# TOF_Module_v02.net
KiCad netlist of a schematic drawn in EasyEDA Pro
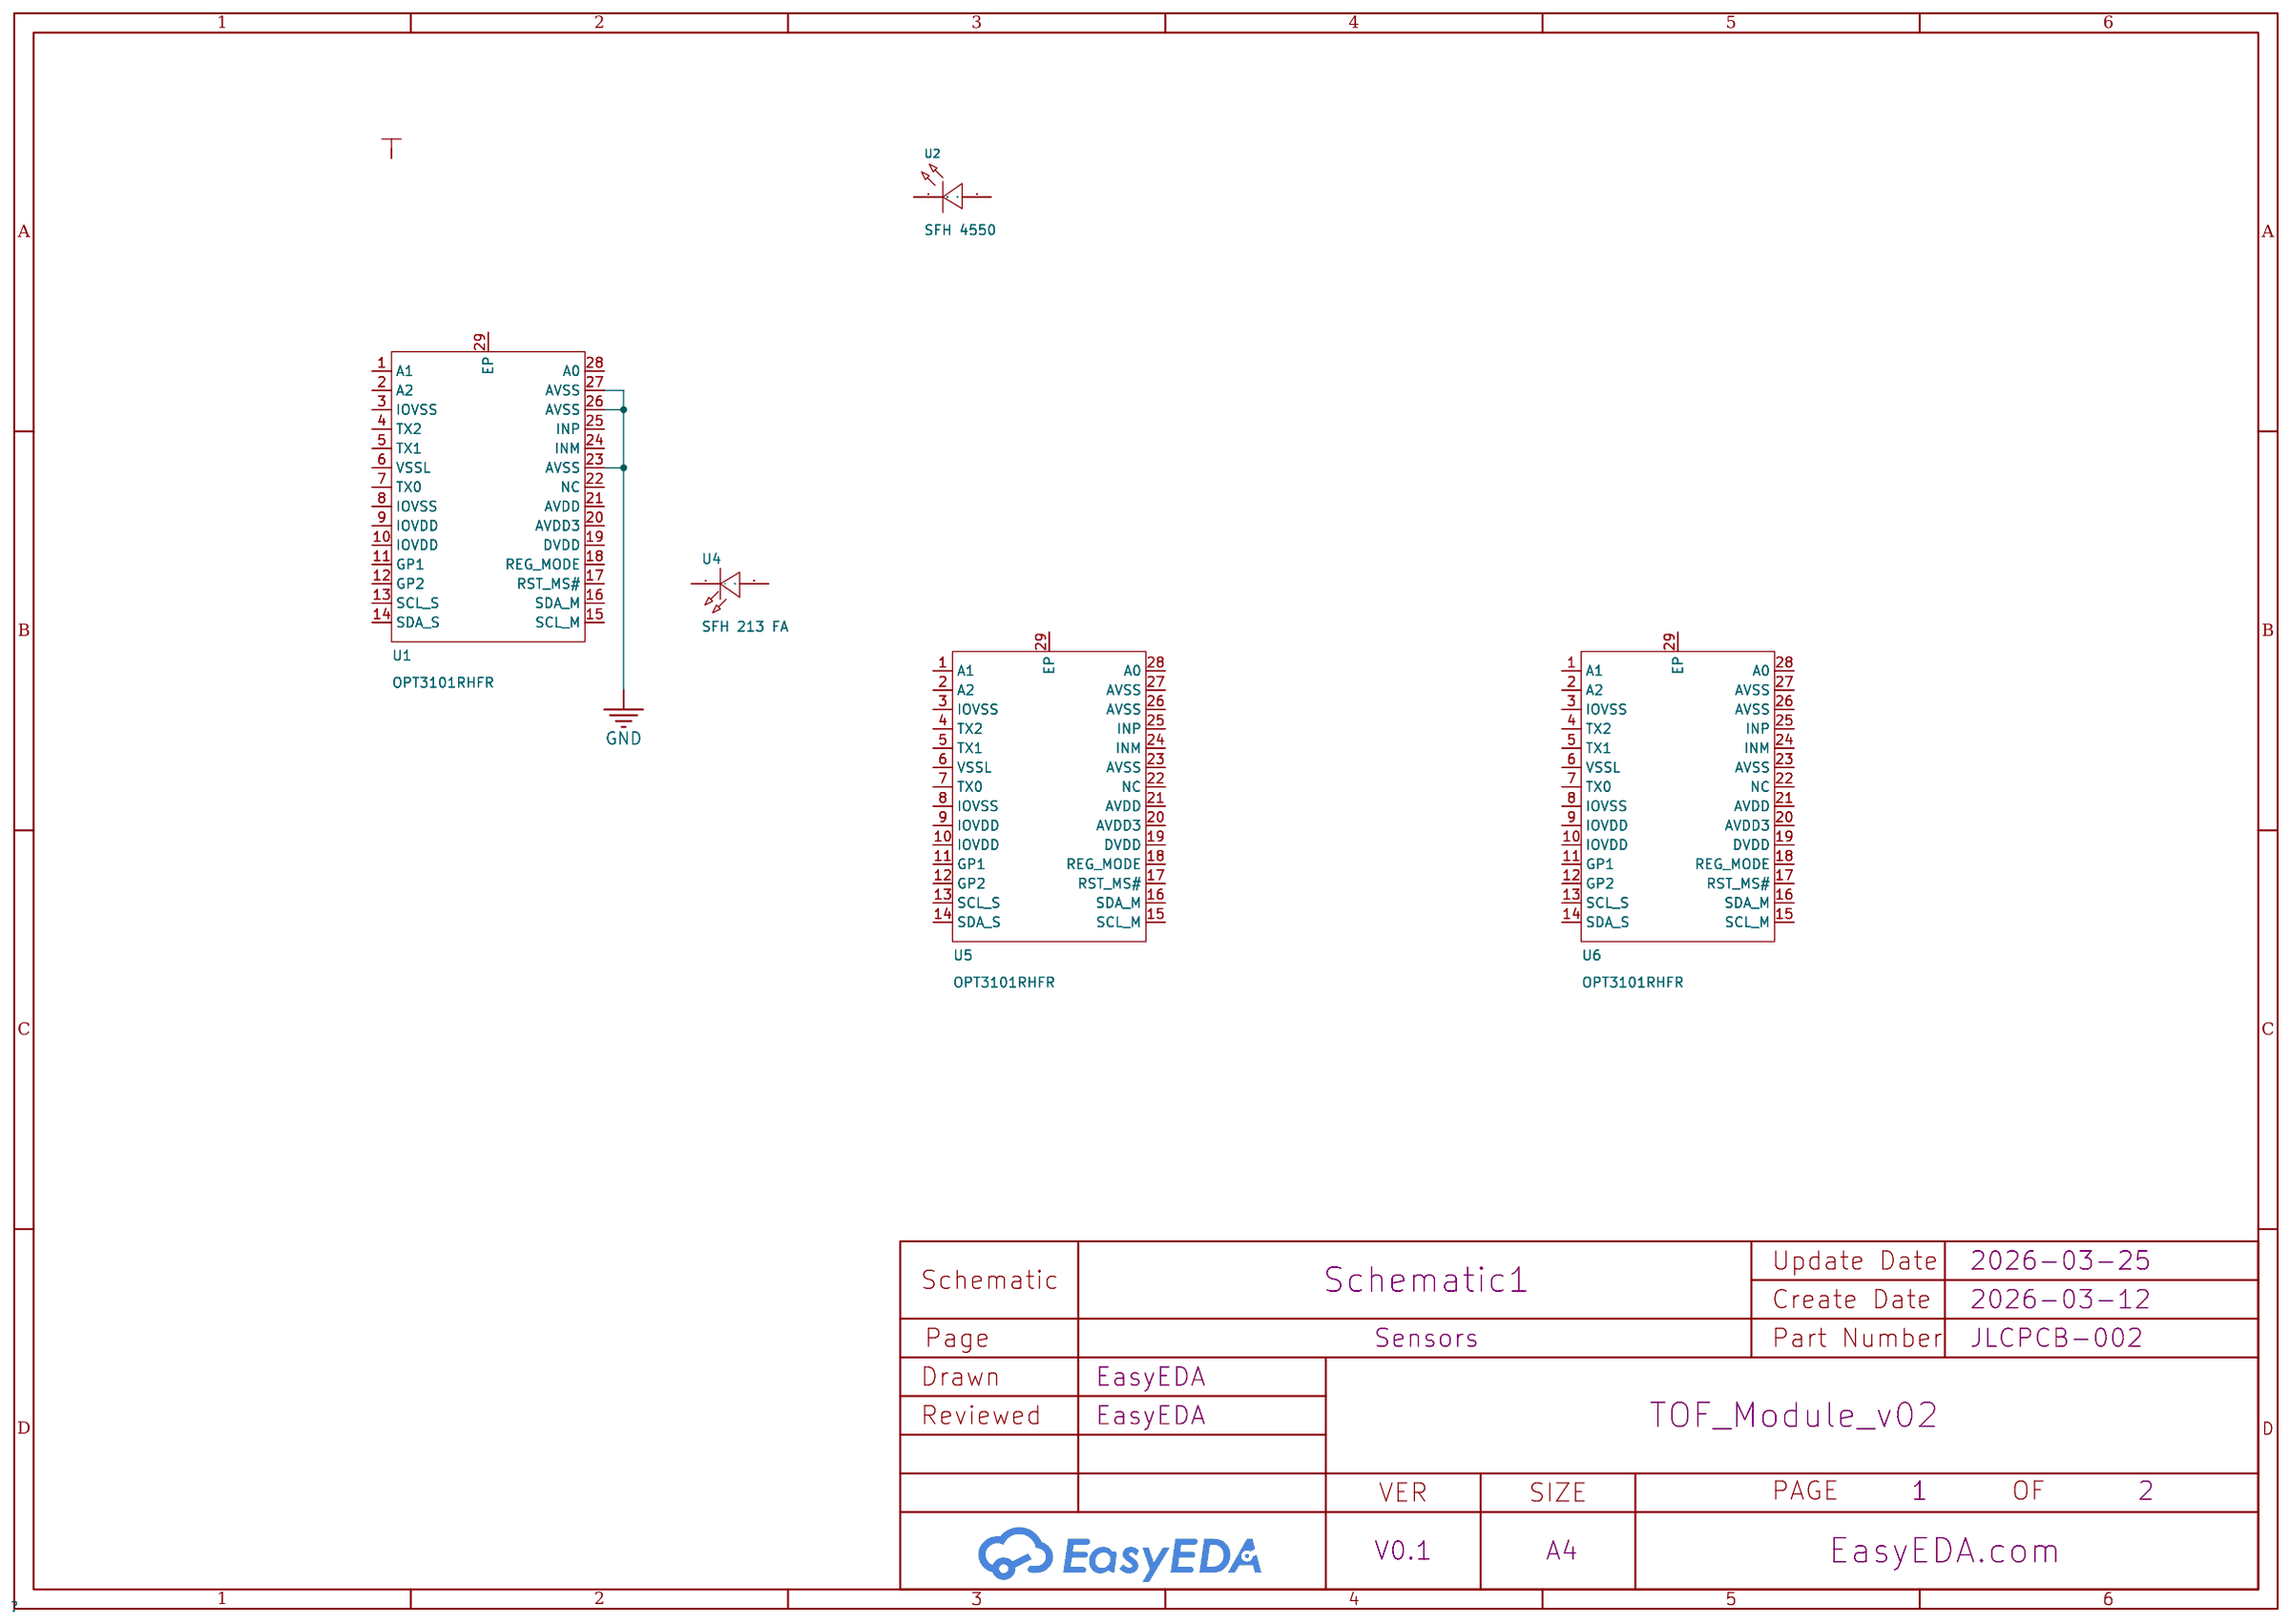
[diagram p0: Sensors]
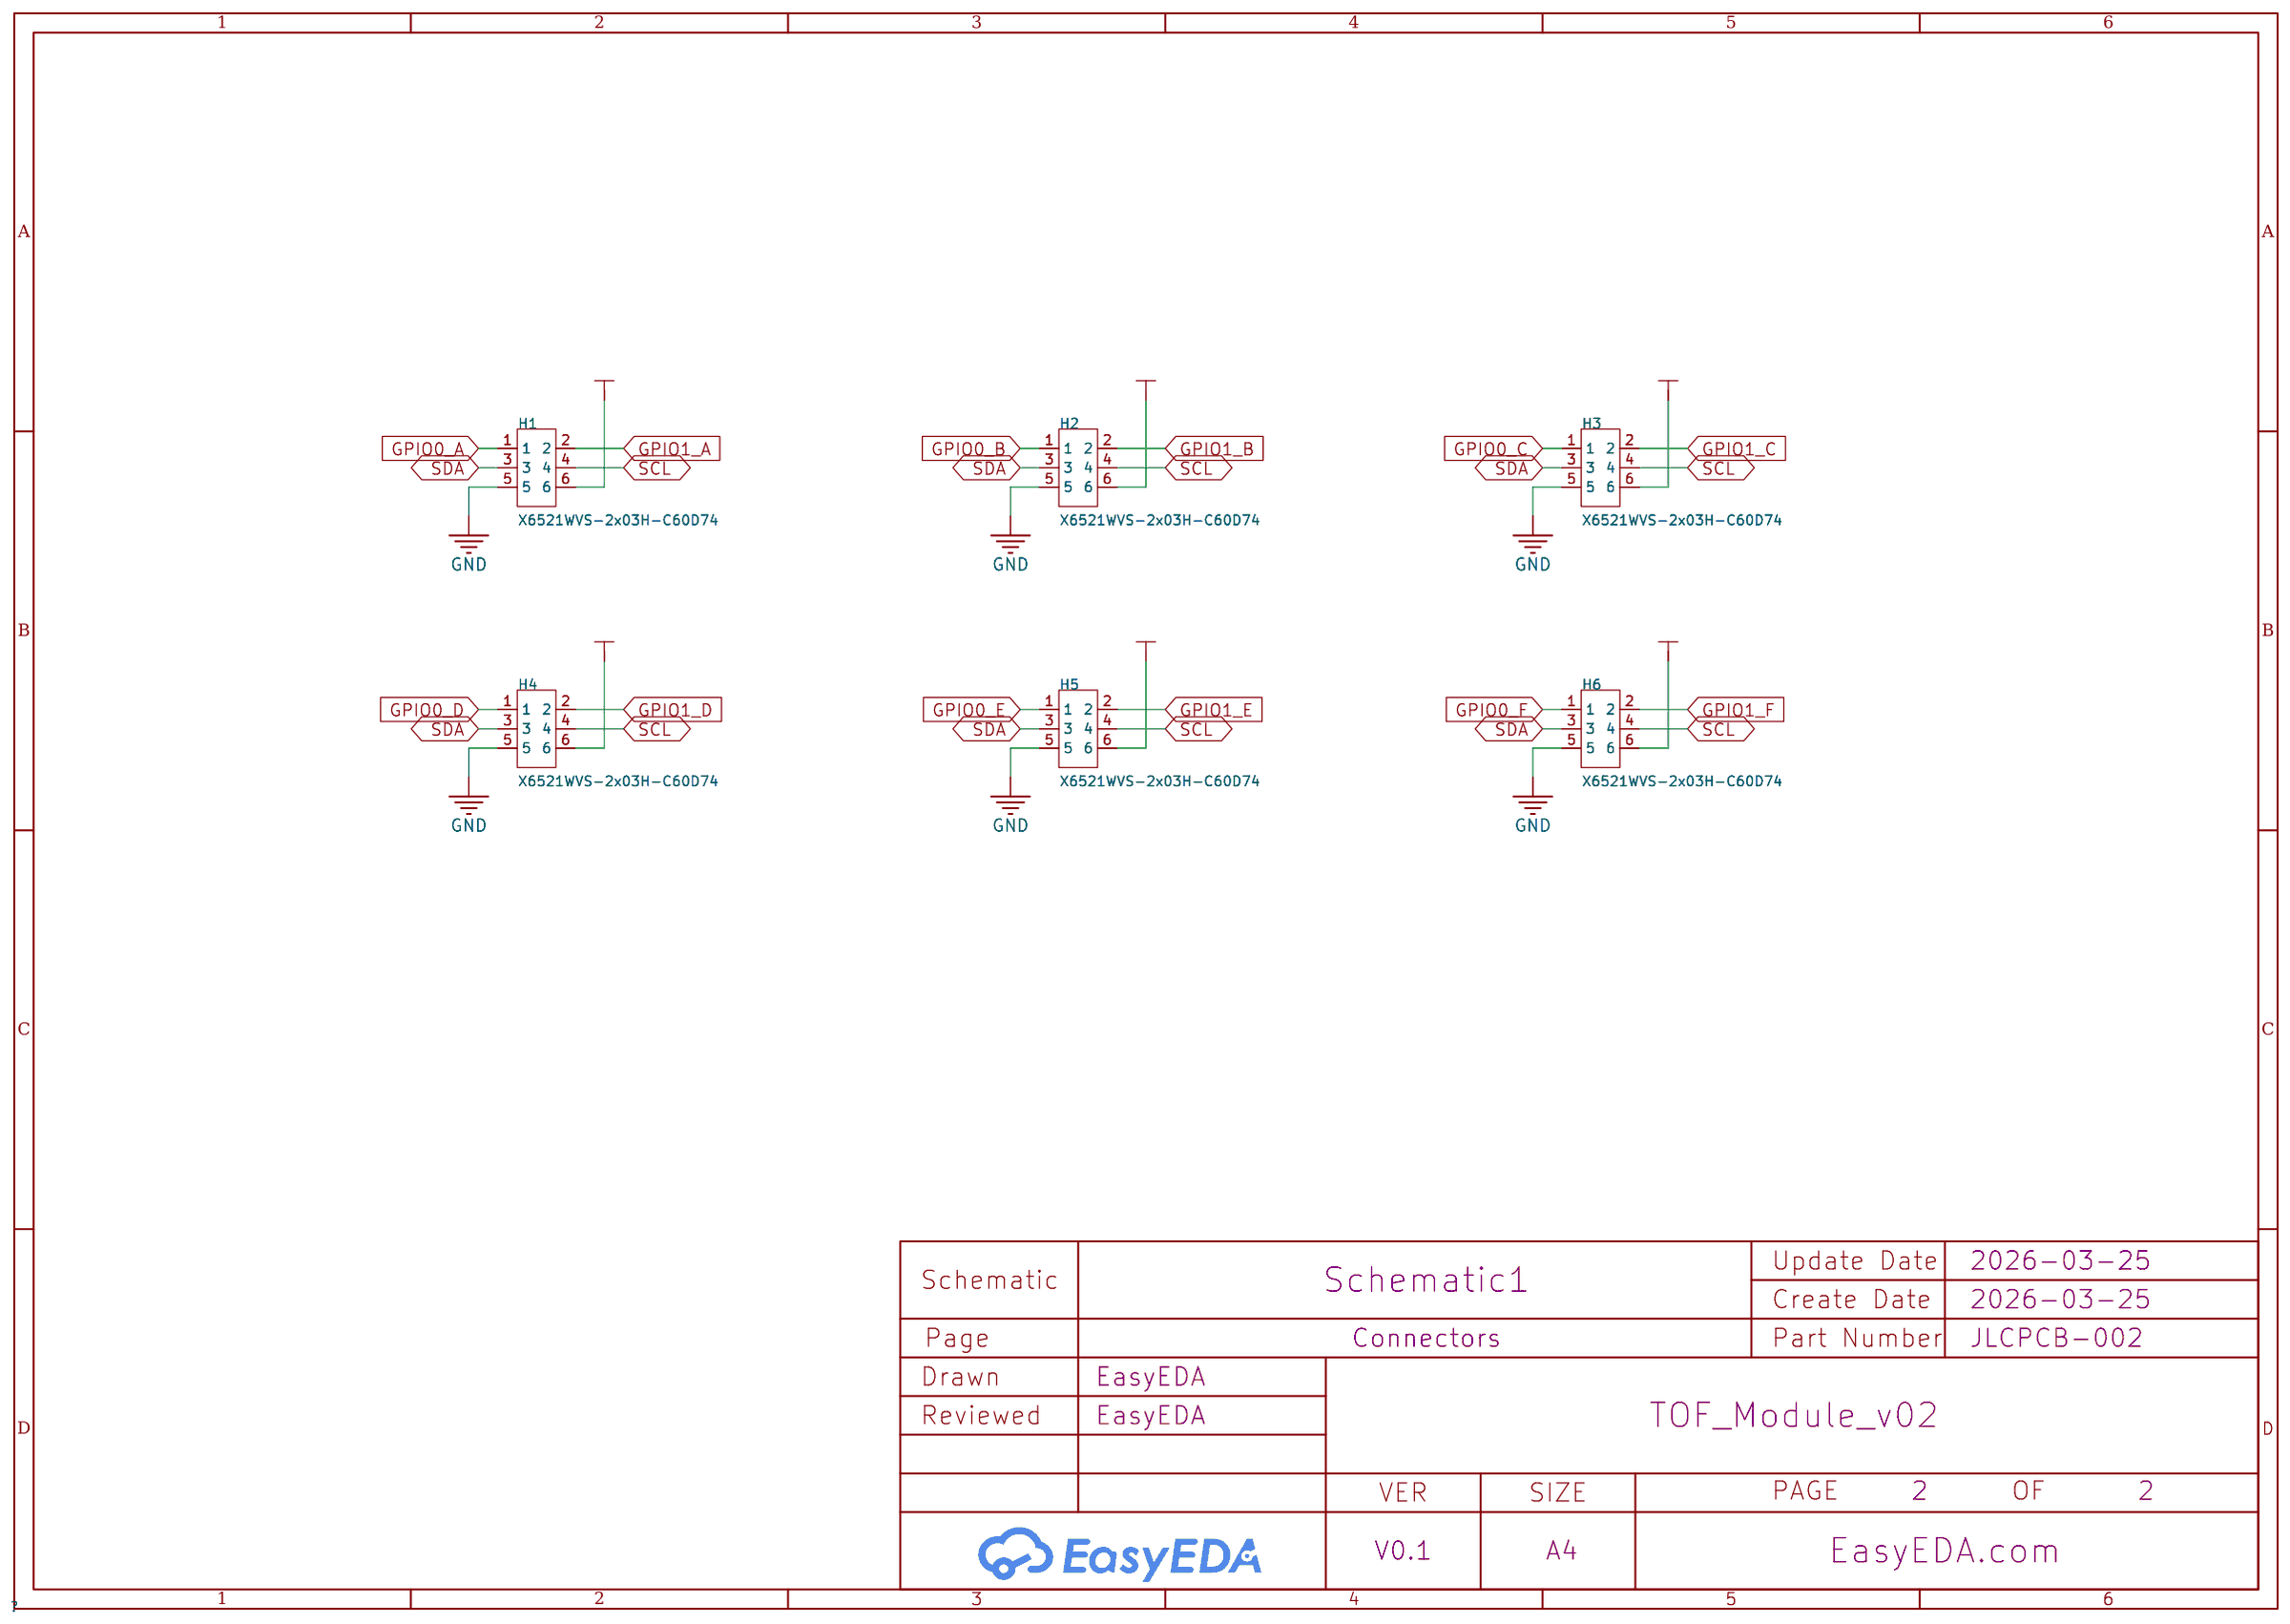
[diagram p1: Connectors]

(export (version "E")
  (design (tool "Eeschema 10.0.6"))
  (components
    (comp (ref "U1")
      (value "OPT3101RHFR")
      (footprint "easyedapro:QFN-28_L5.0-W4.0-P0.50-BL-EP")
      (fields (field (name "Manufacturer") "TI(德州仪器)"))
      (libsource (lib "easyedapro") (part "OPT3101RHFR"))
    )
    (comp (ref "U2")
      (value "SFH 4550")
      (footprint "easyedapro:LED-TH_BD5.9-P2.54-RD")
      (fields (field (name "Manufacturer") "OSRAM(欧司朗)"))
      (libsource (lib "easyedapro") (part "SFH 4550"))
    )
    (comp (ref "U4")
      (value "SFH 213 FA")
      (footprint "easyedapro:OPTO-TH_BD5.8-P2.54-R-FD")
      (fields (field (name "Manufacturer") "OSRAM(欧司朗)"))
      (libsource (lib "easyedapro") (part "SFH 213 FA"))
    )
    (comp (ref "U5")
      (value "OPT3101RHFR")
      (footprint "easyedapro:QFN-28_L5.0-W4.0-P0.50-BL-EP")
      (fields (field (name "Manufacturer") "TI(德州仪器)"))
      (libsource (lib "easyedapro") (part "OPT3101RHFR"))
    )
    (comp (ref "U6")
      (value "OPT3101RHFR")
      (footprint "easyedapro:QFN-28_L5.0-W4.0-P0.50-BL-EP")
      (fields (field (name "Manufacturer") "TI(德州仪器)"))
      (libsource (lib "easyedapro") (part "OPT3101RHFR"))
    )
    (comp (ref "H1")
      (value "X6521WVS-2x03H-C60D74")
      (footprint "easyedapro:HDR-SMD_6P-P2.54-V-M-R2-C5-S7.4")
      (fields (field (name "Manufacturer") "XKB Connection(中国星坤)"))
      (libsource (lib "easyedapro") (part "X6521WVS-2*03H-C60D74"))
    )
    (comp (ref "H2")
      (value "X6521WVS-2x03H-C60D74")
      (footprint "easyedapro:HDR-SMD_6P-P2.54-V-M-R2-C5-S7.4")
      (fields (field (name "Manufacturer") "XKB Connection(中国星坤)"))
      (libsource (lib "easyedapro") (part "X6521WVS-2*03H-C60D74"))
    )
    (comp (ref "H3")
      (value "X6521WVS-2x03H-C60D74")
      (footprint "easyedapro:HDR-SMD_6P-P2.54-V-M-R2-C5-S7.4")
      (fields (field (name "Manufacturer") "XKB Connection(中国星坤)"))
      (libsource (lib "easyedapro") (part "X6521WVS-2*03H-C60D74"))
    )
    (comp (ref "H4")
      (value "X6521WVS-2x03H-C60D74")
      (footprint "easyedapro:HDR-SMD_6P-P2.54-V-M-R2-C5-S7.4")
      (fields (field (name "Manufacturer") "XKB Connection(中国星坤)"))
      (libsource (lib "easyedapro") (part "X6521WVS-2*03H-C60D74"))
    )
    (comp (ref "H5")
      (value "X6521WVS-2x03H-C60D74")
      (footprint "easyedapro:HDR-SMD_6P-P2.54-V-M-R2-C5-S7.4")
      (fields (field (name "Manufacturer") "XKB Connection(中国星坤)"))
      (libsource (lib "easyedapro") (part "X6521WVS-2*03H-C60D74"))
    )
    (comp (ref "H6")
      (value "X6521WVS-2x03H-C60D74")
      (footprint "easyedapro:HDR-SMD_6P-P2.54-V-M-R2-C5-S7.4")
      (fields (field (name "Manufacturer") "XKB Connection(中国星坤)"))
      (libsource (lib "easyedapro") (part "X6521WVS-2*03H-C60D74"))
    )
  )
  (nets
    (net (code "1") (name "3V3") (class "Default")
      (node (ref "H1") (pin "6") (pinfunction "6_6") (pintype "unspecified"))
      (node (ref "H2") (pin "6") (pinfunction "6_6") (pintype "unspecified"))
      (node (ref "H3") (pin "6") (pinfunction "6_6") (pintype "unspecified"))
      (node (ref "H4") (pin "6") (pinfunction "6_6") (pintype "unspecified"))
      (node (ref "H5") (pin "6") (pinfunction "6_6") (pintype "unspecified"))
      (node (ref "H6") (pin "6") (pinfunction "6_6") (pintype "unspecified"))
    )
    (net (code "2") (name "GND") (class "Default")
      (node (ref "H1") (pin "5") (pinfunction "5_5") (pintype "unspecified"))
      (node (ref "H2") (pin "5") (pinfunction "5_5") (pintype "unspecified"))
      (node (ref "H3") (pin "5") (pinfunction "5_5") (pintype "unspecified"))
      (node (ref "H4") (pin "5") (pinfunction "5_5") (pintype "unspecified"))
      (node (ref "H5") (pin "5") (pinfunction "5_5") (pintype "unspecified"))
      (node (ref "H6") (pin "5") (pinfunction "5_5") (pintype "unspecified"))
      (node (ref "U1") (pin "23") (pinfunction "AVSS_23") (pintype "unspecified"))
      (node (ref "U1") (pin "26") (pinfunction "AVSS_26") (pintype "unspecified"))
      (node (ref "U1") (pin "27") (pinfunction "AVSS_27") (pintype "unspecified"))
    )
    (net (code "3") (name "GPIO0_A") (class "Default")
      (node (ref "H1") (pin "1") (pinfunction "1_1") (pintype "unspecified"))
    )
    (net (code "4") (name "GPIO0_B") (class "Default")
      (node (ref "H2") (pin "1") (pinfunction "1_1") (pintype "unspecified"))
    )
    (net (code "5") (name "GPIO0_C") (class "Default")
      (node (ref "H3") (pin "1") (pinfunction "1_1") (pintype "unspecified"))
    )
    (net (code "6") (name "GPIO0_D") (class "Default")
      (node (ref "H4") (pin "1") (pinfunction "1_1") (pintype "unspecified"))
    )
    (net (code "7") (name "GPIO0_E") (class "Default")
      (node (ref "H5") (pin "1") (pinfunction "1_1") (pintype "unspecified"))
    )
    (net (code "8") (name "GPIO0_F") (class "Default")
      (node (ref "H6") (pin "1") (pinfunction "1_1") (pintype "unspecified"))
    )
    (net (code "9") (name "GPIO1_A") (class "Default")
      (node (ref "H1") (pin "2") (pinfunction "2_2") (pintype "unspecified"))
    )
    (net (code "10") (name "GPIO1_B") (class "Default")
      (node (ref "H2") (pin "2") (pinfunction "2_2") (pintype "unspecified"))
    )
    (net (code "11") (name "GPIO1_C") (class "Default")
      (node (ref "H3") (pin "2") (pinfunction "2_2") (pintype "unspecified"))
    )
    (net (code "12") (name "GPIO1_D") (class "Default")
      (node (ref "H4") (pin "2") (pinfunction "2_2") (pintype "unspecified"))
    )
    (net (code "13") (name "GPIO1_E") (class "Default")
      (node (ref "H5") (pin "2") (pinfunction "2_2") (pintype "unspecified"))
    )
    (net (code "14") (name "GPIO1_F") (class "Default")
      (node (ref "H6") (pin "2") (pinfunction "2_2") (pintype "unspecified"))
    )
    (net (code "15") (name "SCL") (class "Default")
      (node (ref "H1") (pin "4") (pinfunction "4_4") (pintype "unspecified"))
      (node (ref "H2") (pin "4") (pinfunction "4_4") (pintype "unspecified"))
      (node (ref "H3") (pin "4") (pinfunction "4_4") (pintype "unspecified"))
      (node (ref "H4") (pin "4") (pinfunction "4_4") (pintype "unspecified"))
      (node (ref "H5") (pin "4") (pinfunction "4_4") (pintype "unspecified"))
      (node (ref "H6") (pin "4") (pinfunction "4_4") (pintype "unspecified"))
    )
    (net (code "16") (name "SDA") (class "Default")
      (node (ref "H1") (pin "3") (pinfunction "3_3") (pintype "unspecified"))
      (node (ref "H2") (pin "3") (pinfunction "3_3") (pintype "unspecified"))
      (node (ref "H3") (pin "3") (pinfunction "3_3") (pintype "unspecified"))
      (node (ref "H4") (pin "3") (pinfunction "3_3") (pintype "unspecified"))
      (node (ref "H5") (pin "3") (pinfunction "3_3") (pintype "unspecified"))
      (node (ref "H6") (pin "3") (pinfunction "3_3") (pintype "unspecified"))
    )
    (net (code "17") (name "unconnected-(U1-A0-Pad28)") (class "Default")
      (node (ref "U1") (pin "28") (pinfunction "A0_28") (pintype "unspecified"))
    )
    (net (code "18") (name "unconnected-(U1-A1-Pad1)") (class "Default")
      (node (ref "U1") (pin "1") (pinfunction "A1_1") (pintype "unspecified"))
    )
    (net (code "19") (name "unconnected-(U1-A2-Pad2)") (class "Default")
      (node (ref "U1") (pin "2") (pinfunction "A2_2") (pintype "unspecified"))
    )
    (net (code "20") (name "unconnected-(U1-AVDD-Pad21)") (class "Default")
      (node (ref "U1") (pin "21") (pinfunction "AVDD_21") (pintype "unspecified"))
    )
    (net (code "21") (name "unconnected-(U1-AVDD3-Pad20)") (class "Default")
      (node (ref "U1") (pin "20") (pinfunction "AVDD3_20") (pintype "unspecified"))
    )
    (net (code "22") (name "unconnected-(U1-DVDD-Pad19)") (class "Default")
      (node (ref "U1") (pin "19") (pinfunction "DVDD_19") (pintype "unspecified"))
    )
    (net (code "23") (name "unconnected-(U1-EP-Pad29)") (class "Default")
      (node (ref "U1") (pin "29") (pinfunction "EP_29") (pintype "unspecified"))
    )
    (net (code "24") (name "unconnected-(U1-GP1-Pad11)") (class "Default")
      (node (ref "U1") (pin "11") (pinfunction "GP1_11") (pintype "unspecified"))
    )
    (net (code "25") (name "unconnected-(U1-GP2-Pad12)") (class "Default")
      (node (ref "U1") (pin "12") (pinfunction "GP2_12") (pintype "unspecified"))
    )
    (net (code "26") (name "unconnected-(U1-INM-Pad24)") (class "Default")
      (node (ref "U1") (pin "24") (pinfunction "INM_24") (pintype "unspecified"))
    )
    (net (code "27") (name "unconnected-(U1-INP-Pad25)") (class "Default")
      (node (ref "U1") (pin "25") (pinfunction "INP_25") (pintype "unspecified"))
    )
    (net (code "28") (name "unconnected-(U1-IOVDD-Pad9)") (class "Default")
      (node (ref "U1") (pin "9") (pinfunction "IOVDD_9") (pintype "unspecified"))
    )
    (net (code "29") (name "unconnected-(U1-IOVDD-Pad10)") (class "Default")
      (node (ref "U1") (pin "10") (pinfunction "IOVDD_10") (pintype "unspecified"))
    )
    (net (code "30") (name "unconnected-(U1-IOVSS-Pad3)") (class "Default")
      (node (ref "U1") (pin "3") (pinfunction "IOVSS_3") (pintype "unspecified"))
    )
    (net (code "31") (name "unconnected-(U1-IOVSS-Pad8)") (class "Default")
      (node (ref "U1") (pin "8") (pinfunction "IOVSS_8") (pintype "unspecified"))
    )
    (net (code "32") (name "unconnected-(U1-NC-Pad22)") (class "Default")
      (node (ref "U1") (pin "22") (pinfunction "NC_22") (pintype "unspecified"))
    )
    (net (code "33") (name "unconnected-(U1-REG_MODE-Pad18)") (class "Default")
      (node (ref "U1") (pin "18") (pinfunction "REG_MODE_18") (pintype "unspecified"))
    )
    (net (code "34") (name "unconnected-(U1-RST_MS#-Pad17)") (class "Default")
      (node (ref "U1") (pin "17") (pinfunction "RST_MS#_17") (pintype "unspecified"))
    )
    (net (code "35") (name "unconnected-(U1-SCL_M-Pad15)") (class "Default")
      (node (ref "U1") (pin "15") (pinfunction "SCL_M_15") (pintype "unspecified"))
    )
    (net (code "36") (name "unconnected-(U1-SCL_S-Pad13)") (class "Default")
      (node (ref "U1") (pin "13") (pinfunction "SCL_S_13") (pintype "unspecified"))
    )
    (net (code "37") (name "unconnected-(U1-SDA_M-Pad16)") (class "Default")
      (node (ref "U1") (pin "16") (pinfunction "SDA_M_16") (pintype "unspecified"))
    )
    (net (code "38") (name "unconnected-(U1-SDA_S-Pad14)") (class "Default")
      (node (ref "U1") (pin "14") (pinfunction "SDA_S_14") (pintype "unspecified"))
    )
    (net (code "39") (name "unconnected-(U1-TX0-Pad7)") (class "Default")
      (node (ref "U1") (pin "7") (pinfunction "TX0_7") (pintype "unspecified"))
    )
    (net (code "40") (name "unconnected-(U1-TX1-Pad5)") (class "Default")
      (node (ref "U1") (pin "5") (pinfunction "TX1_5") (pintype "unspecified"))
    )
    (net (code "41") (name "unconnected-(U1-TX2-Pad4)") (class "Default")
      (node (ref "U1") (pin "4") (pinfunction "TX2_4") (pintype "unspecified"))
    )
    (net (code "42") (name "unconnected-(U1-VSSL-Pad6)") (class "Default")
      (node (ref "U1") (pin "6") (pinfunction "VSSL_6") (pintype "unspecified"))
    )
    (net (code "43") (name "unconnected-(U2-Pad1)") (class "Default")
      (node (ref "U2") (pin "1") (pinfunction "1_1") (pintype "input"))
    )
    (net (code "44") (name "unconnected-(U2-Pad2)") (class "Default")
      (node (ref "U2") (pin "2") (pinfunction "2_2") (pintype "input"))
    )
    (net (code "45") (name "unconnected-(U4-+-Pad2)") (class "Default")
      (node (ref "U4") (pin "2") (pinfunction "+_2") (pintype "unspecified"))
    )
    (net (code "46") (name "unconnected-(U4---Pad1)") (class "Default")
      (node (ref "U4") (pin "1") (pinfunction "-_1") (pintype "unspecified"))
    )
    (net (code "47") (name "unconnected-(U5-A0-Pad28)") (class "Default")
      (node (ref "U5") (pin "28") (pinfunction "A0_28") (pintype "unspecified"))
    )
    (net (code "48") (name "unconnected-(U5-A1-Pad1)") (class "Default")
      (node (ref "U5") (pin "1") (pinfunction "A1_1") (pintype "unspecified"))
    )
    (net (code "49") (name "unconnected-(U5-A2-Pad2)") (class "Default")
      (node (ref "U5") (pin "2") (pinfunction "A2_2") (pintype "unspecified"))
    )
    (net (code "50") (name "unconnected-(U5-AVDD-Pad21)") (class "Default")
      (node (ref "U5") (pin "21") (pinfunction "AVDD_21") (pintype "unspecified"))
    )
    (net (code "51") (name "unconnected-(U5-AVDD3-Pad20)") (class "Default")
      (node (ref "U5") (pin "20") (pinfunction "AVDD3_20") (pintype "unspecified"))
    )
    (net (code "52") (name "unconnected-(U5-AVSS-Pad23)") (class "Default")
      (node (ref "U5") (pin "23") (pinfunction "AVSS_23") (pintype "unspecified"))
    )
    (net (code "53") (name "unconnected-(U5-AVSS-Pad26)") (class "Default")
      (node (ref "U5") (pin "26") (pinfunction "AVSS_26") (pintype "unspecified"))
    )
    (net (code "54") (name "unconnected-(U5-AVSS-Pad27)") (class "Default")
      (node (ref "U5") (pin "27") (pinfunction "AVSS_27") (pintype "unspecified"))
    )
    (net (code "55") (name "unconnected-(U5-DVDD-Pad19)") (class "Default")
      (node (ref "U5") (pin "19") (pinfunction "DVDD_19") (pintype "unspecified"))
    )
    (net (code "56") (name "unconnected-(U5-EP-Pad29)") (class "Default")
      (node (ref "U5") (pin "29") (pinfunction "EP_29") (pintype "unspecified"))
    )
    (net (code "57") (name "unconnected-(U5-GP1-Pad11)") (class "Default")
      (node (ref "U5") (pin "11") (pinfunction "GP1_11") (pintype "unspecified"))
    )
    (net (code "58") (name "unconnected-(U5-GP2-Pad12)") (class "Default")
      (node (ref "U5") (pin "12") (pinfunction "GP2_12") (pintype "unspecified"))
    )
    (net (code "59") (name "unconnected-(U5-INM-Pad24)") (class "Default")
      (node (ref "U5") (pin "24") (pinfunction "INM_24") (pintype "unspecified"))
    )
    (net (code "60") (name "unconnected-(U5-INP-Pad25)") (class "Default")
      (node (ref "U5") (pin "25") (pinfunction "INP_25") (pintype "unspecified"))
    )
    (net (code "61") (name "unconnected-(U5-IOVDD-Pad9)") (class "Default")
      (node (ref "U5") (pin "9") (pinfunction "IOVDD_9") (pintype "unspecified"))
    )
    (net (code "62") (name "unconnected-(U5-IOVDD-Pad10)") (class "Default")
      (node (ref "U5") (pin "10") (pinfunction "IOVDD_10") (pintype "unspecified"))
    )
    (net (code "63") (name "unconnected-(U5-IOVSS-Pad3)") (class "Default")
      (node (ref "U5") (pin "3") (pinfunction "IOVSS_3") (pintype "unspecified"))
    )
    (net (code "64") (name "unconnected-(U5-IOVSS-Pad8)") (class "Default")
      (node (ref "U5") (pin "8") (pinfunction "IOVSS_8") (pintype "unspecified"))
    )
    (net (code "65") (name "unconnected-(U5-NC-Pad22)") (class "Default")
      (node (ref "U5") (pin "22") (pinfunction "NC_22") (pintype "unspecified"))
    )
    (net (code "66") (name "unconnected-(U5-REG_MODE-Pad18)") (class "Default")
      (node (ref "U5") (pin "18") (pinfunction "REG_MODE_18") (pintype "unspecified"))
    )
    (net (code "67") (name "unconnected-(U5-RST_MS#-Pad17)") (class "Default")
      (node (ref "U5") (pin "17") (pinfunction "RST_MS#_17") (pintype "unspecified"))
    )
    (net (code "68") (name "unconnected-(U5-SCL_M-Pad15)") (class "Default")
      (node (ref "U5") (pin "15") (pinfunction "SCL_M_15") (pintype "unspecified"))
    )
    (net (code "69") (name "unconnected-(U5-SCL_S-Pad13)") (class "Default")
      (node (ref "U5") (pin "13") (pinfunction "SCL_S_13") (pintype "unspecified"))
    )
    (net (code "70") (name "unconnected-(U5-SDA_M-Pad16)") (class "Default")
      (node (ref "U5") (pin "16") (pinfunction "SDA_M_16") (pintype "unspecified"))
    )
    (net (code "71") (name "unconnected-(U5-SDA_S-Pad14)") (class "Default")
      (node (ref "U5") (pin "14") (pinfunction "SDA_S_14") (pintype "unspecified"))
    )
    (net (code "72") (name "unconnected-(U5-TX0-Pad7)") (class "Default")
      (node (ref "U5") (pin "7") (pinfunction "TX0_7") (pintype "unspecified"))
    )
    (net (code "73") (name "unconnected-(U5-TX1-Pad5)") (class "Default")
      (node (ref "U5") (pin "5") (pinfunction "TX1_5") (pintype "unspecified"))
    )
    (net (code "74") (name "unconnected-(U5-TX2-Pad4)") (class "Default")
      (node (ref "U5") (pin "4") (pinfunction "TX2_4") (pintype "unspecified"))
    )
    (net (code "75") (name "unconnected-(U5-VSSL-Pad6)") (class "Default")
      (node (ref "U5") (pin "6") (pinfunction "VSSL_6") (pintype "unspecified"))
    )
    (net (code "76") (name "unconnected-(U6-A0-Pad28)") (class "Default")
      (node (ref "U6") (pin "28") (pinfunction "A0_28") (pintype "unspecified"))
    )
    (net (code "77") (name "unconnected-(U6-A1-Pad1)") (class "Default")
      (node (ref "U6") (pin "1") (pinfunction "A1_1") (pintype "unspecified"))
    )
    (net (code "78") (name "unconnected-(U6-A2-Pad2)") (class "Default")
      (node (ref "U6") (pin "2") (pinfunction "A2_2") (pintype "unspecified"))
    )
    (net (code "79") (name "unconnected-(U6-AVDD-Pad21)") (class "Default")
      (node (ref "U6") (pin "21") (pinfunction "AVDD_21") (pintype "unspecified"))
    )
    (net (code "80") (name "unconnected-(U6-AVDD3-Pad20)") (class "Default")
      (node (ref "U6") (pin "20") (pinfunction "AVDD3_20") (pintype "unspecified"))
    )
    (net (code "81") (name "unconnected-(U6-AVSS-Pad23)") (class "Default")
      (node (ref "U6") (pin "23") (pinfunction "AVSS_23") (pintype "unspecified"))
    )
    (net (code "82") (name "unconnected-(U6-AVSS-Pad26)") (class "Default")
      (node (ref "U6") (pin "26") (pinfunction "AVSS_26") (pintype "unspecified"))
    )
    (net (code "83") (name "unconnected-(U6-AVSS-Pad27)") (class "Default")
      (node (ref "U6") (pin "27") (pinfunction "AVSS_27") (pintype "unspecified"))
    )
    (net (code "84") (name "unconnected-(U6-DVDD-Pad19)") (class "Default")
      (node (ref "U6") (pin "19") (pinfunction "DVDD_19") (pintype "unspecified"))
    )
    (net (code "85") (name "unconnected-(U6-EP-Pad29)") (class "Default")
      (node (ref "U6") (pin "29") (pinfunction "EP_29") (pintype "unspecified"))
    )
    (net (code "86") (name "unconnected-(U6-GP1-Pad11)") (class "Default")
      (node (ref "U6") (pin "11") (pinfunction "GP1_11") (pintype "unspecified"))
    )
    (net (code "87") (name "unconnected-(U6-GP2-Pad12)") (class "Default")
      (node (ref "U6") (pin "12") (pinfunction "GP2_12") (pintype "unspecified"))
    )
    (net (code "88") (name "unconnected-(U6-INM-Pad24)") (class "Default")
      (node (ref "U6") (pin "24") (pinfunction "INM_24") (pintype "unspecified"))
    )
    (net (code "89") (name "unconnected-(U6-INP-Pad25)") (class "Default")
      (node (ref "U6") (pin "25") (pinfunction "INP_25") (pintype "unspecified"))
    )
    (net (code "90") (name "unconnected-(U6-IOVDD-Pad9)") (class "Default")
      (node (ref "U6") (pin "9") (pinfunction "IOVDD_9") (pintype "unspecified"))
    )
    (net (code "91") (name "unconnected-(U6-IOVDD-Pad10)") (class "Default")
      (node (ref "U6") (pin "10") (pinfunction "IOVDD_10") (pintype "unspecified"))
    )
    (net (code "92") (name "unconnected-(U6-IOVSS-Pad3)") (class "Default")
      (node (ref "U6") (pin "3") (pinfunction "IOVSS_3") (pintype "unspecified"))
    )
    (net (code "93") (name "unconnected-(U6-IOVSS-Pad8)") (class "Default")
      (node (ref "U6") (pin "8") (pinfunction "IOVSS_8") (pintype "unspecified"))
    )
    (net (code "94") (name "unconnected-(U6-NC-Pad22)") (class "Default")
      (node (ref "U6") (pin "22") (pinfunction "NC_22") (pintype "unspecified"))
    )
    (net (code "95") (name "unconnected-(U6-REG_MODE-Pad18)") (class "Default")
      (node (ref "U6") (pin "18") (pinfunction "REG_MODE_18") (pintype "unspecified"))
    )
    (net (code "96") (name "unconnected-(U6-RST_MS#-Pad17)") (class "Default")
      (node (ref "U6") (pin "17") (pinfunction "RST_MS#_17") (pintype "unspecified"))
    )
    (net (code "97") (name "unconnected-(U6-SCL_M-Pad15)") (class "Default")
      (node (ref "U6") (pin "15") (pinfunction "SCL_M_15") (pintype "unspecified"))
    )
    (net (code "98") (name "unconnected-(U6-SCL_S-Pad13)") (class "Default")
      (node (ref "U6") (pin "13") (pinfunction "SCL_S_13") (pintype "unspecified"))
    )
    (net (code "99") (name "unconnected-(U6-SDA_M-Pad16)") (class "Default")
      (node (ref "U6") (pin "16") (pinfunction "SDA_M_16") (pintype "unspecified"))
    )
    (net (code "100") (name "unconnected-(U6-SDA_S-Pad14)") (class "Default")
      (node (ref "U6") (pin "14") (pinfunction "SDA_S_14") (pintype "unspecified"))
    )
    (net (code "101") (name "unconnected-(U6-TX0-Pad7)") (class "Default")
      (node (ref "U6") (pin "7") (pinfunction "TX0_7") (pintype "unspecified"))
    )
    (net (code "102") (name "unconnected-(U6-TX1-Pad5)") (class "Default")
      (node (ref "U6") (pin "5") (pinfunction "TX1_5") (pintype "unspecified"))
    )
    (net (code "103") (name "unconnected-(U6-TX2-Pad4)") (class "Default")
      (node (ref "U6") (pin "4") (pinfunction "TX2_4") (pintype "unspecified"))
    )
    (net (code "104") (name "unconnected-(U6-VSSL-Pad6)") (class "Default")
      (node (ref "U6") (pin "6") (pinfunction "VSSL_6") (pintype "unspecified"))
    )
  )
)
